# SCH_NFC-Card_2024-02-04.net
KiCad netlist of a schematic drawn in EasyEDA
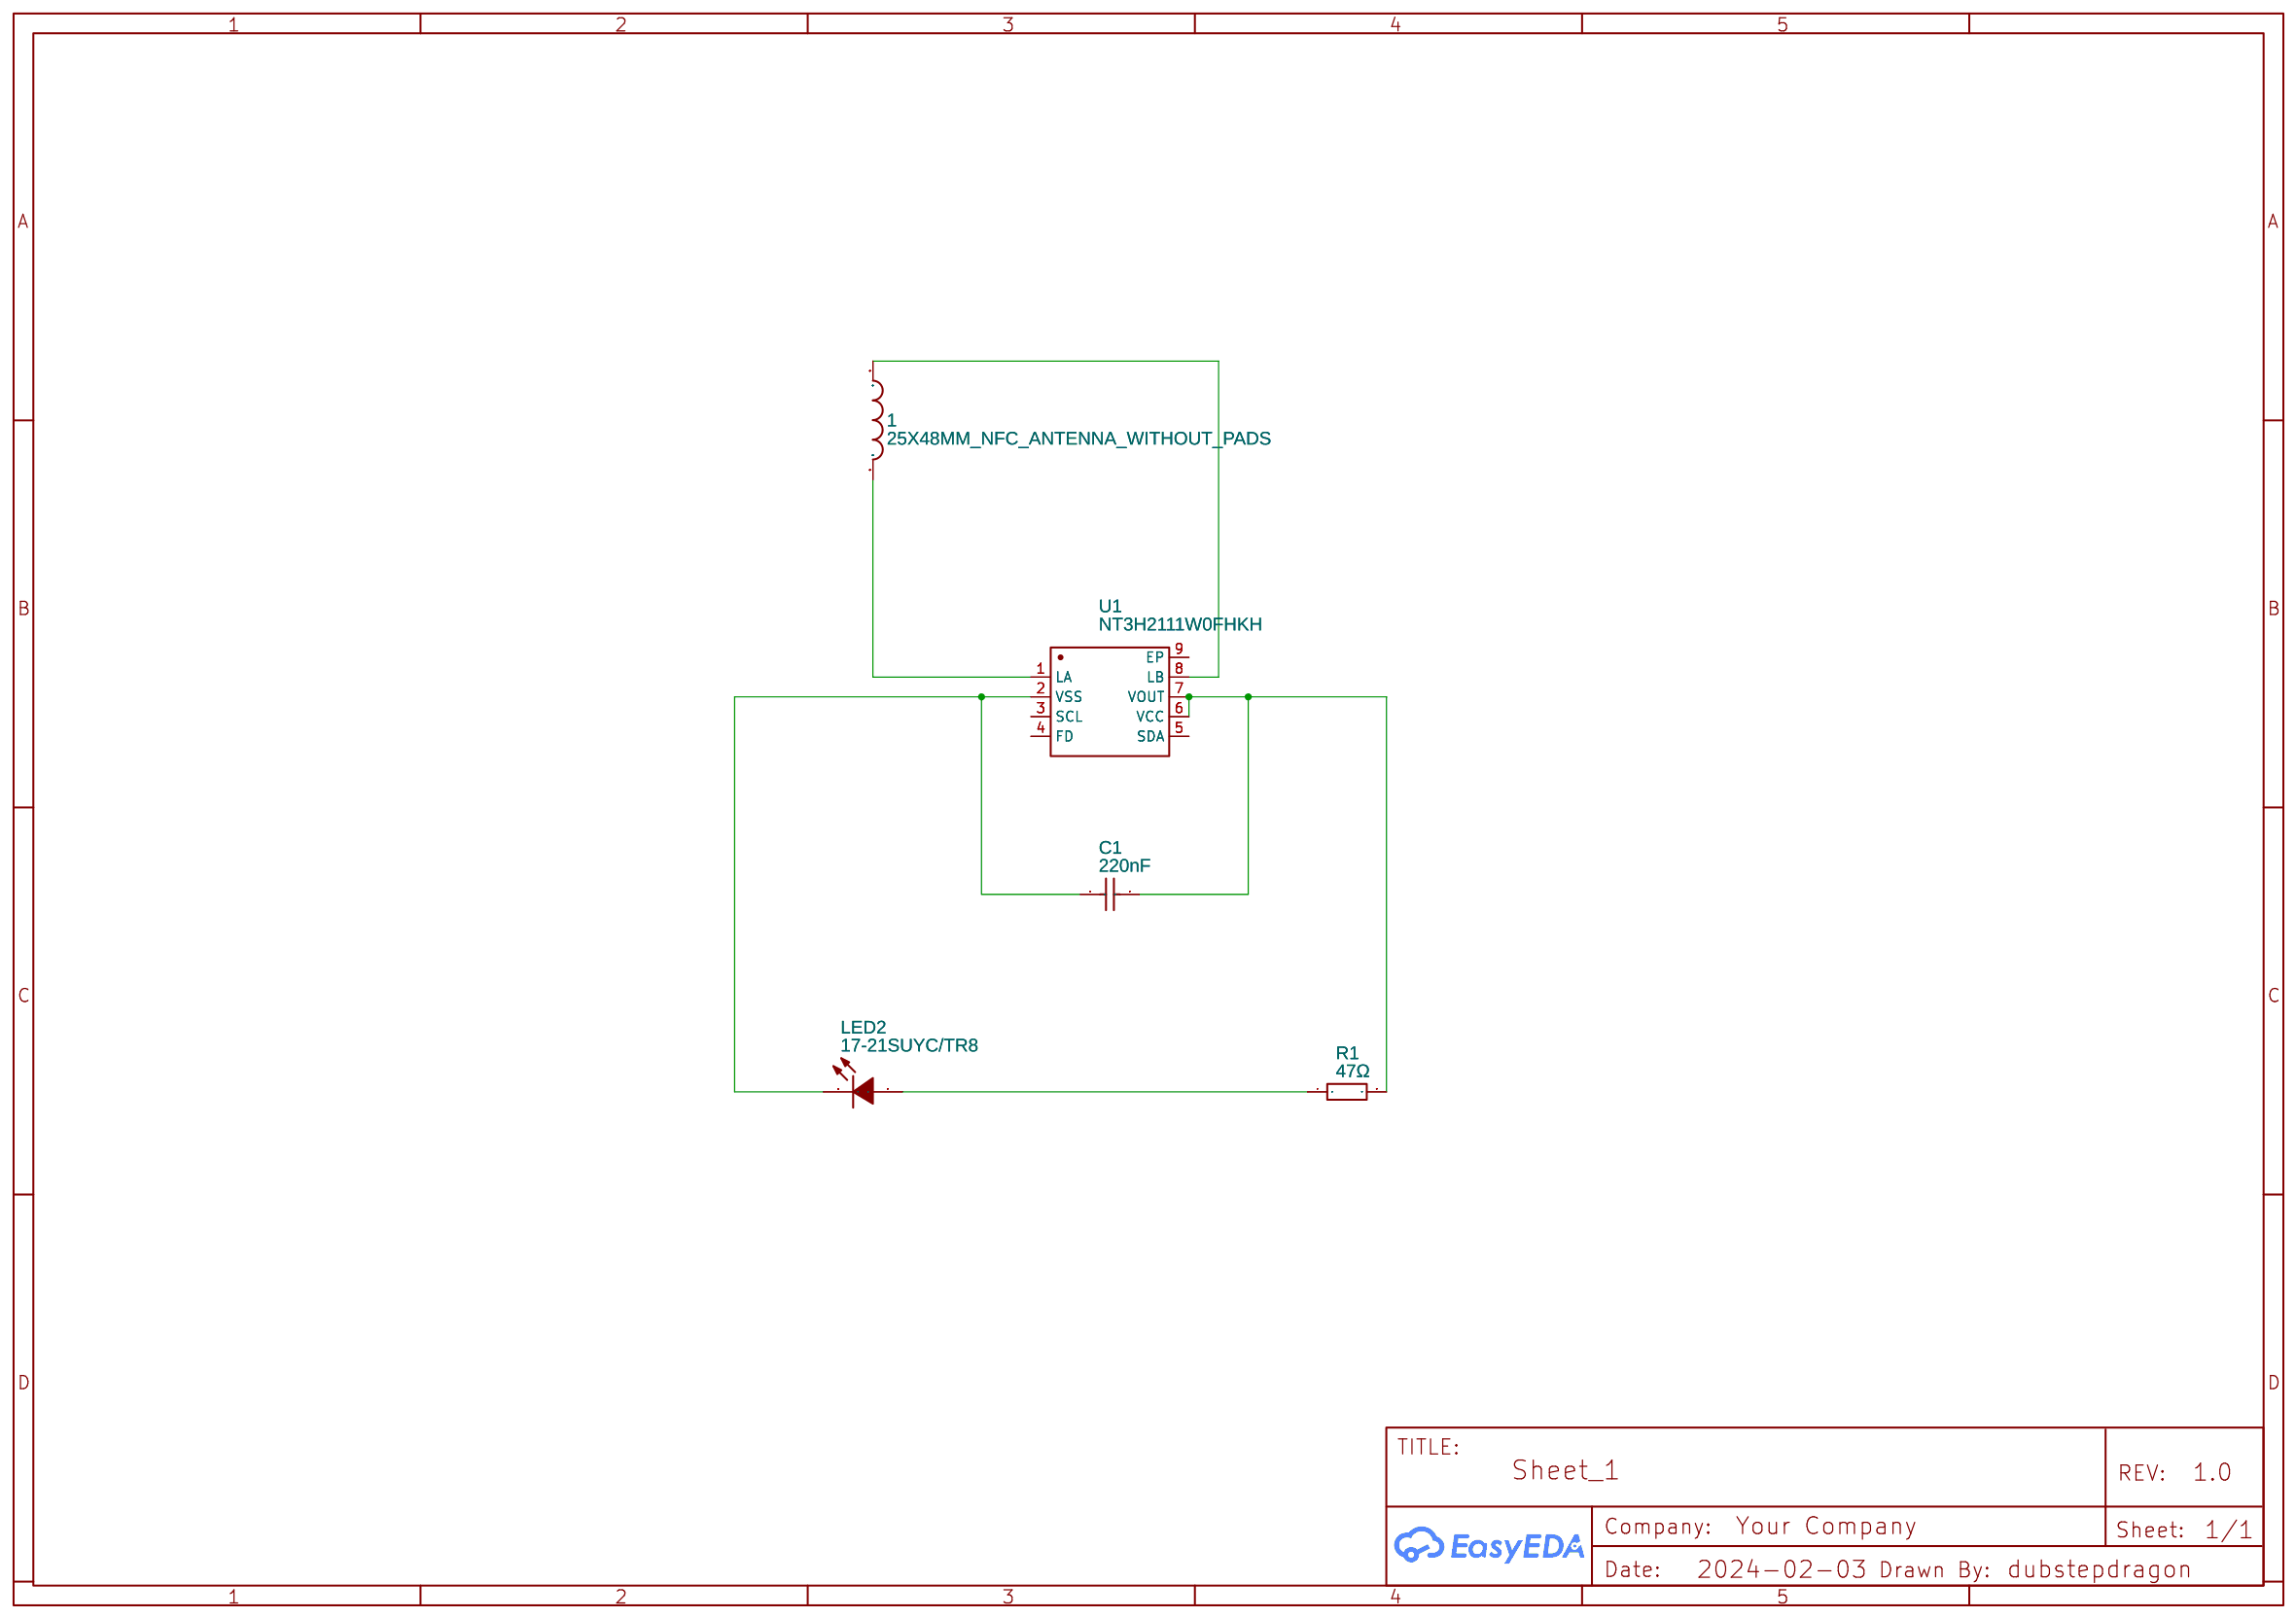
[diagram p0: schematic sheet]

(export (version "E")
  (design (tool "Eeschema 10.0.6"))
  (components
    (comp (ref "1")
      (value "25X48MM_NFC_ANTENNA_WITHOUT_PADS")
      (libsource (lib "") (part "25X48MM_NFC_ANTENNA_WITHOUT_PADS"))
    )
    (comp (ref "C1")
      (value "220nF")
      (fields
        (field (name "Manufacturer Part") "CL10B224KA8NNNC")
        (field (name "Manufacturer") "SAMSUNG(三星)")
      )
      (libsource (lib "") (part "CL10B224KA8NNNC"))
    )
    (comp (ref "LED2")
      (value "17-21SUYC/TR8")
      (fields (field (name "Manufacturer Part") "KT-0805黄灯") (field (name "Manufacturer") "KENTO"))
      (libsource (lib "") (part "17-21SUYC/TR8"))
    )
    (comp (ref "R1")
      (value "47Ω")
      (fields
        (field (name "Manufacturer Part") "0603WAF470JT5E")
        (field (name "Manufacturer") "UNI-ROYAL(厚声)")
      )
      (libsource (lib "") (part "0603WAF470JT5E"))
    )
    (comp (ref "U1")
      (value "NT3H2111W0FHKH")
      (fields (field (name "Manufacturer") "NXP(恩智浦)"))
      (libsource (lib "") (part "NT3H2111W0FHKH"))
    )
  )
  (nets
    (net (code "1") (name "Net-(LED2-+)") (class "Default")
      (node (ref "LED2") (pin "1") (pinfunction "+_1") (pintype "unspecified"))
      (node (ref "R1") (pin "1") (pinfunction "1_1") (pintype "input"))
    )
    (net (code "2") (name "Net-(LED2--)") (class "Default")
      (node (ref "C1") (pin "1") (pinfunction "1_1") (pintype "input"))
      (node (ref "LED2") (pin "2") (pinfunction "-_2") (pintype "unspecified"))
      (node (ref "U1") (pin "2") (pinfunction "VSS_2") (pintype "unspecified"))
    )
    (net (code "3") (name "Net-(U1-LA)") (class "Default")
      (node (ref "1") (pin "P$2") (pinfunction "P$2_P$2") (pintype "bidirectional"))
      (node (ref "U1") (pin "1") (pinfunction "LA_1") (pintype "unspecified"))
    )
    (net (code "4") (name "Net-(U1-LB)") (class "Default")
      (node (ref "1") (pin "P$1") (pinfunction "P$1_P$1") (pintype "bidirectional"))
      (node (ref "U1") (pin "8") (pinfunction "LB_8") (pintype "unspecified"))
    )
    (net (code "5") (name "Net-(U1-VCC)") (class "Default")
      (node (ref "C1") (pin "2") (pinfunction "2_2") (pintype "input"))
      (node (ref "R1") (pin "2") (pinfunction "2_2") (pintype "input"))
      (node (ref "U1") (pin "6") (pinfunction "VCC_6") (pintype "unspecified"))
      (node (ref "U1") (pin "7") (pinfunction "VOUT_7") (pintype "unspecified"))
    )
    (net (code "6") (name "unconnected-(U1-EP-Pad9)") (class "Default")
      (node (ref "U1") (pin "9") (pinfunction "EP_9") (pintype "unspecified"))
    )
    (net (code "7") (name "unconnected-(U1-FD-Pad4)") (class "Default")
      (node (ref "U1") (pin "4") (pinfunction "FD_4") (pintype "unspecified"))
    )
    (net (code "8") (name "unconnected-(U1-SCL-Pad3)") (class "Default")
      (node (ref "U1") (pin "3") (pinfunction "SCL_3") (pintype "unspecified"))
    )
    (net (code "9") (name "unconnected-(U1-SDA-Pad5)") (class "Default")
      (node (ref "U1") (pin "5") (pinfunction "SDA_5") (pintype "unspecified"))
    )
  )
)
